# ControlBoard.net
KiCad netlist of a schematic drawn in EAGLE
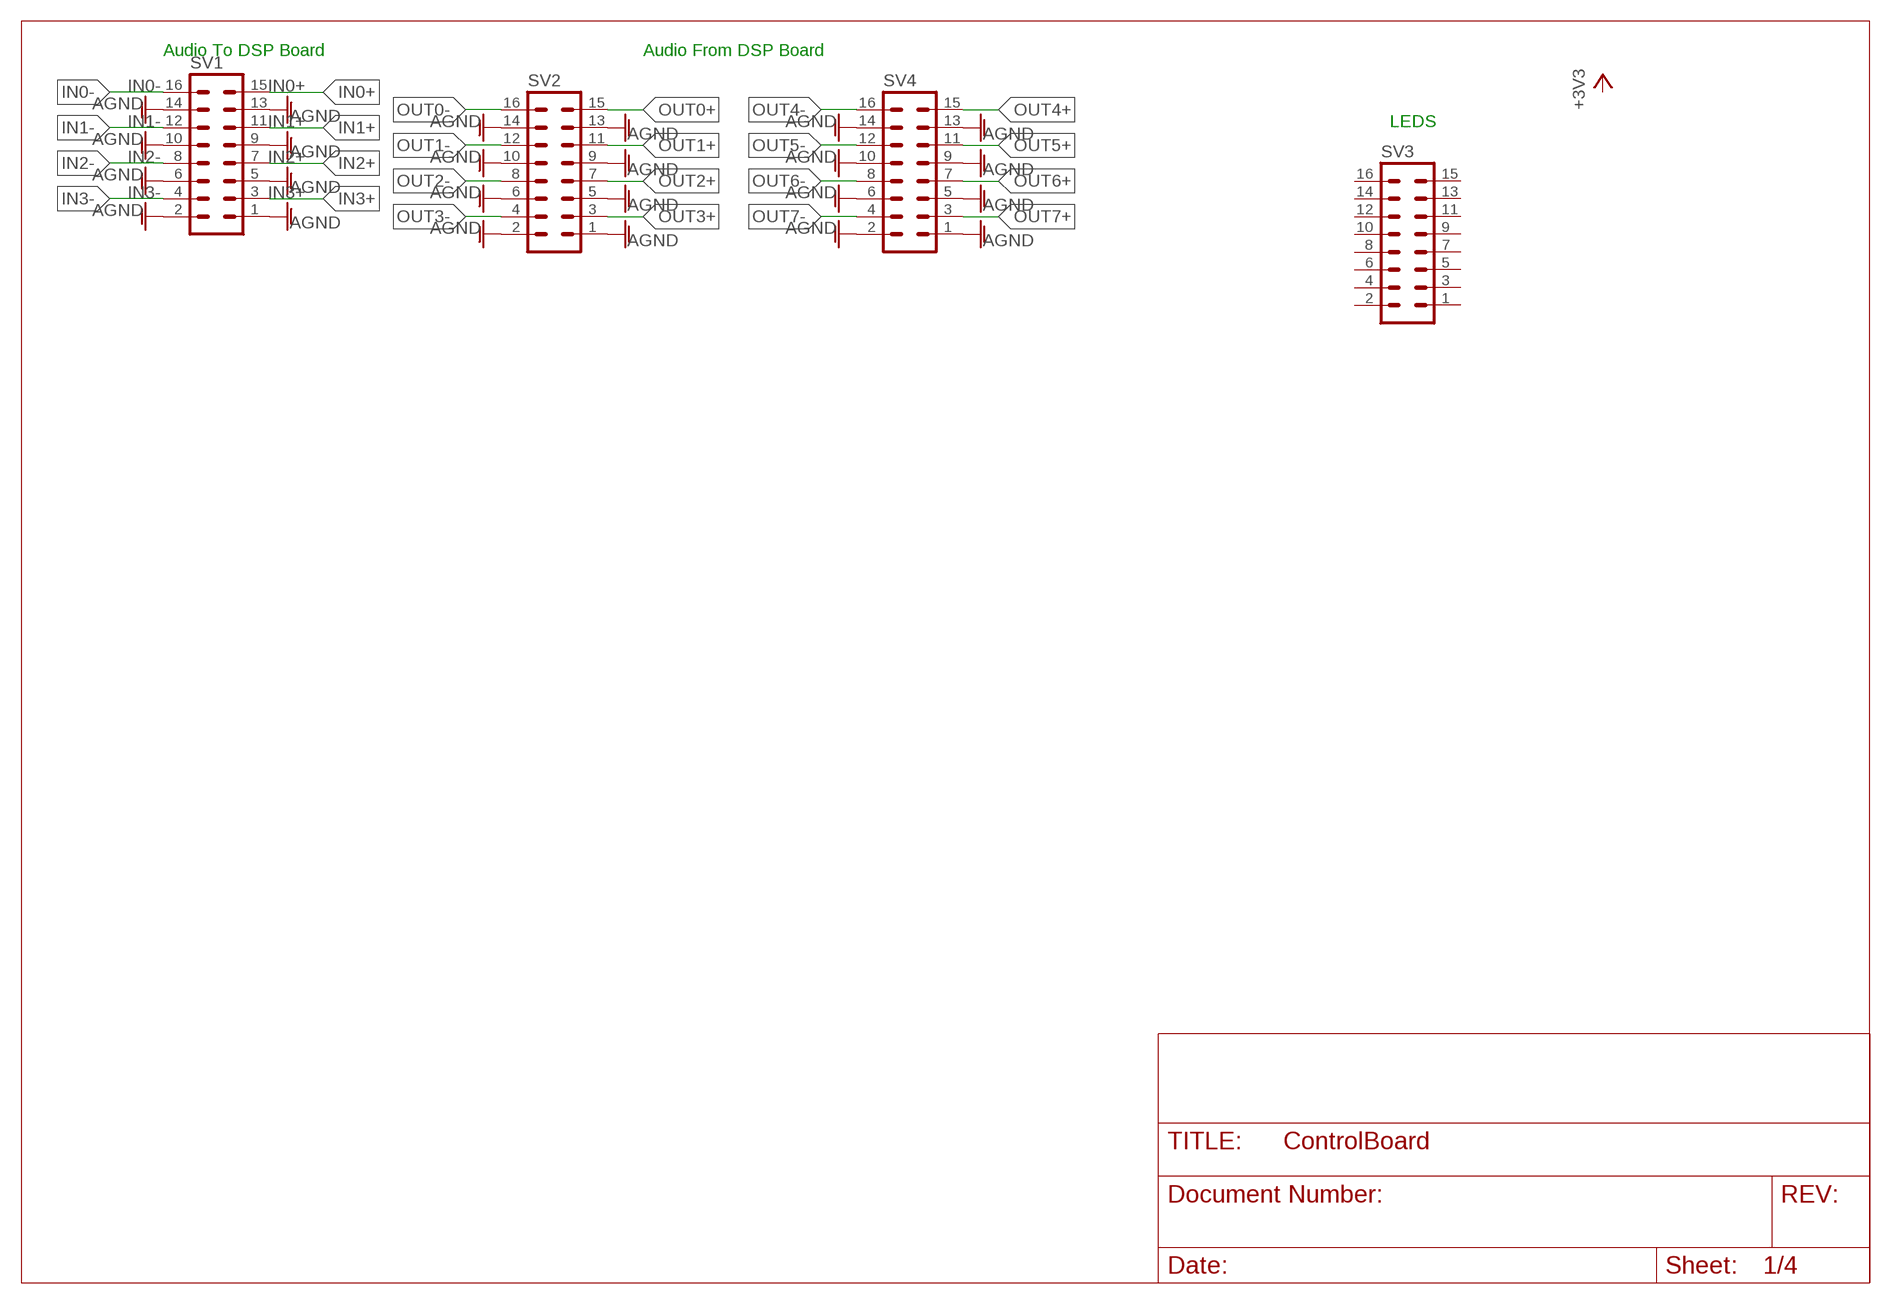
[diagram p0: schematic, sheet 1]
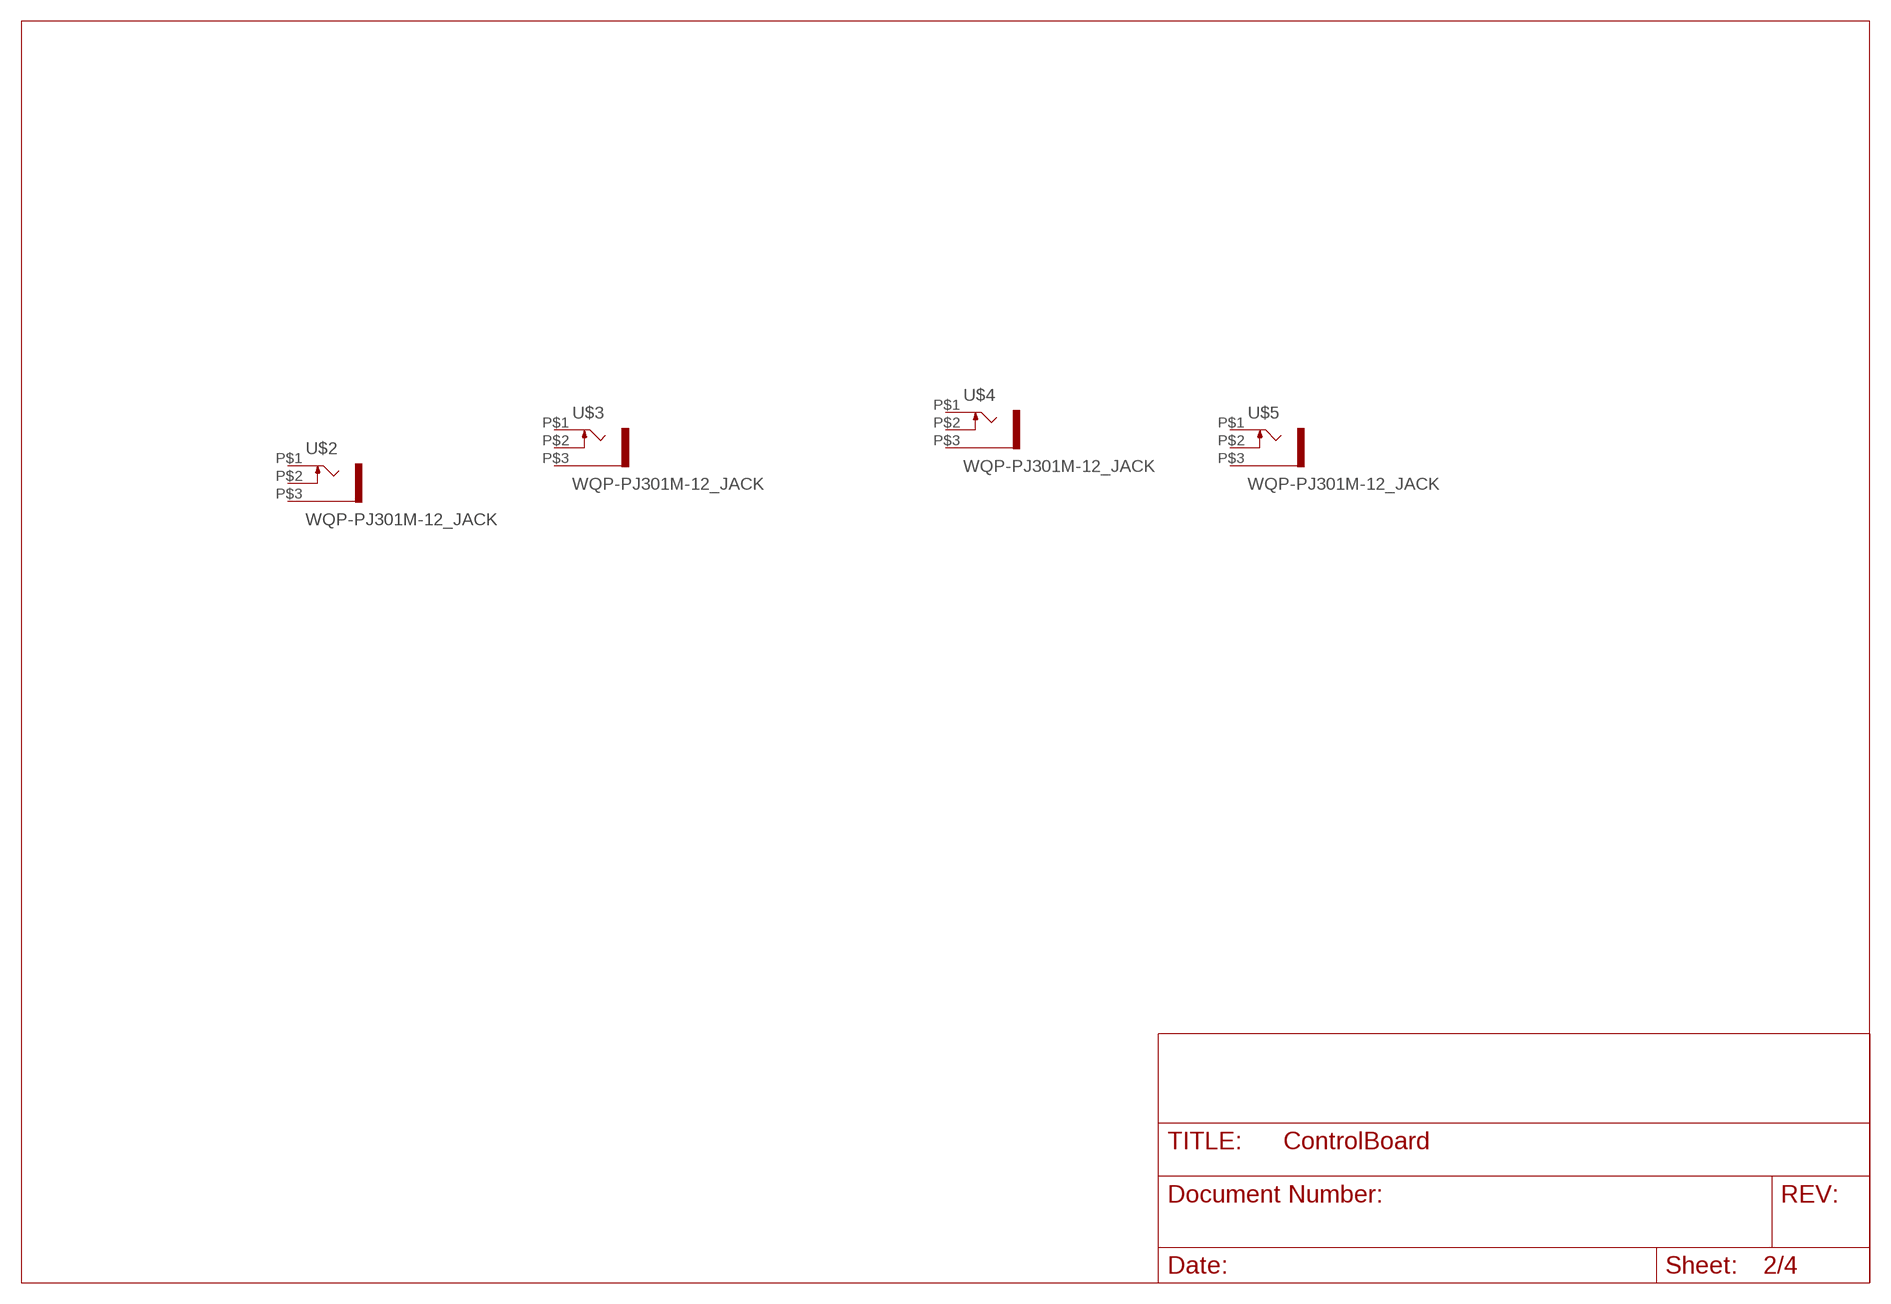
[diagram p1: schematic, sheet 2]
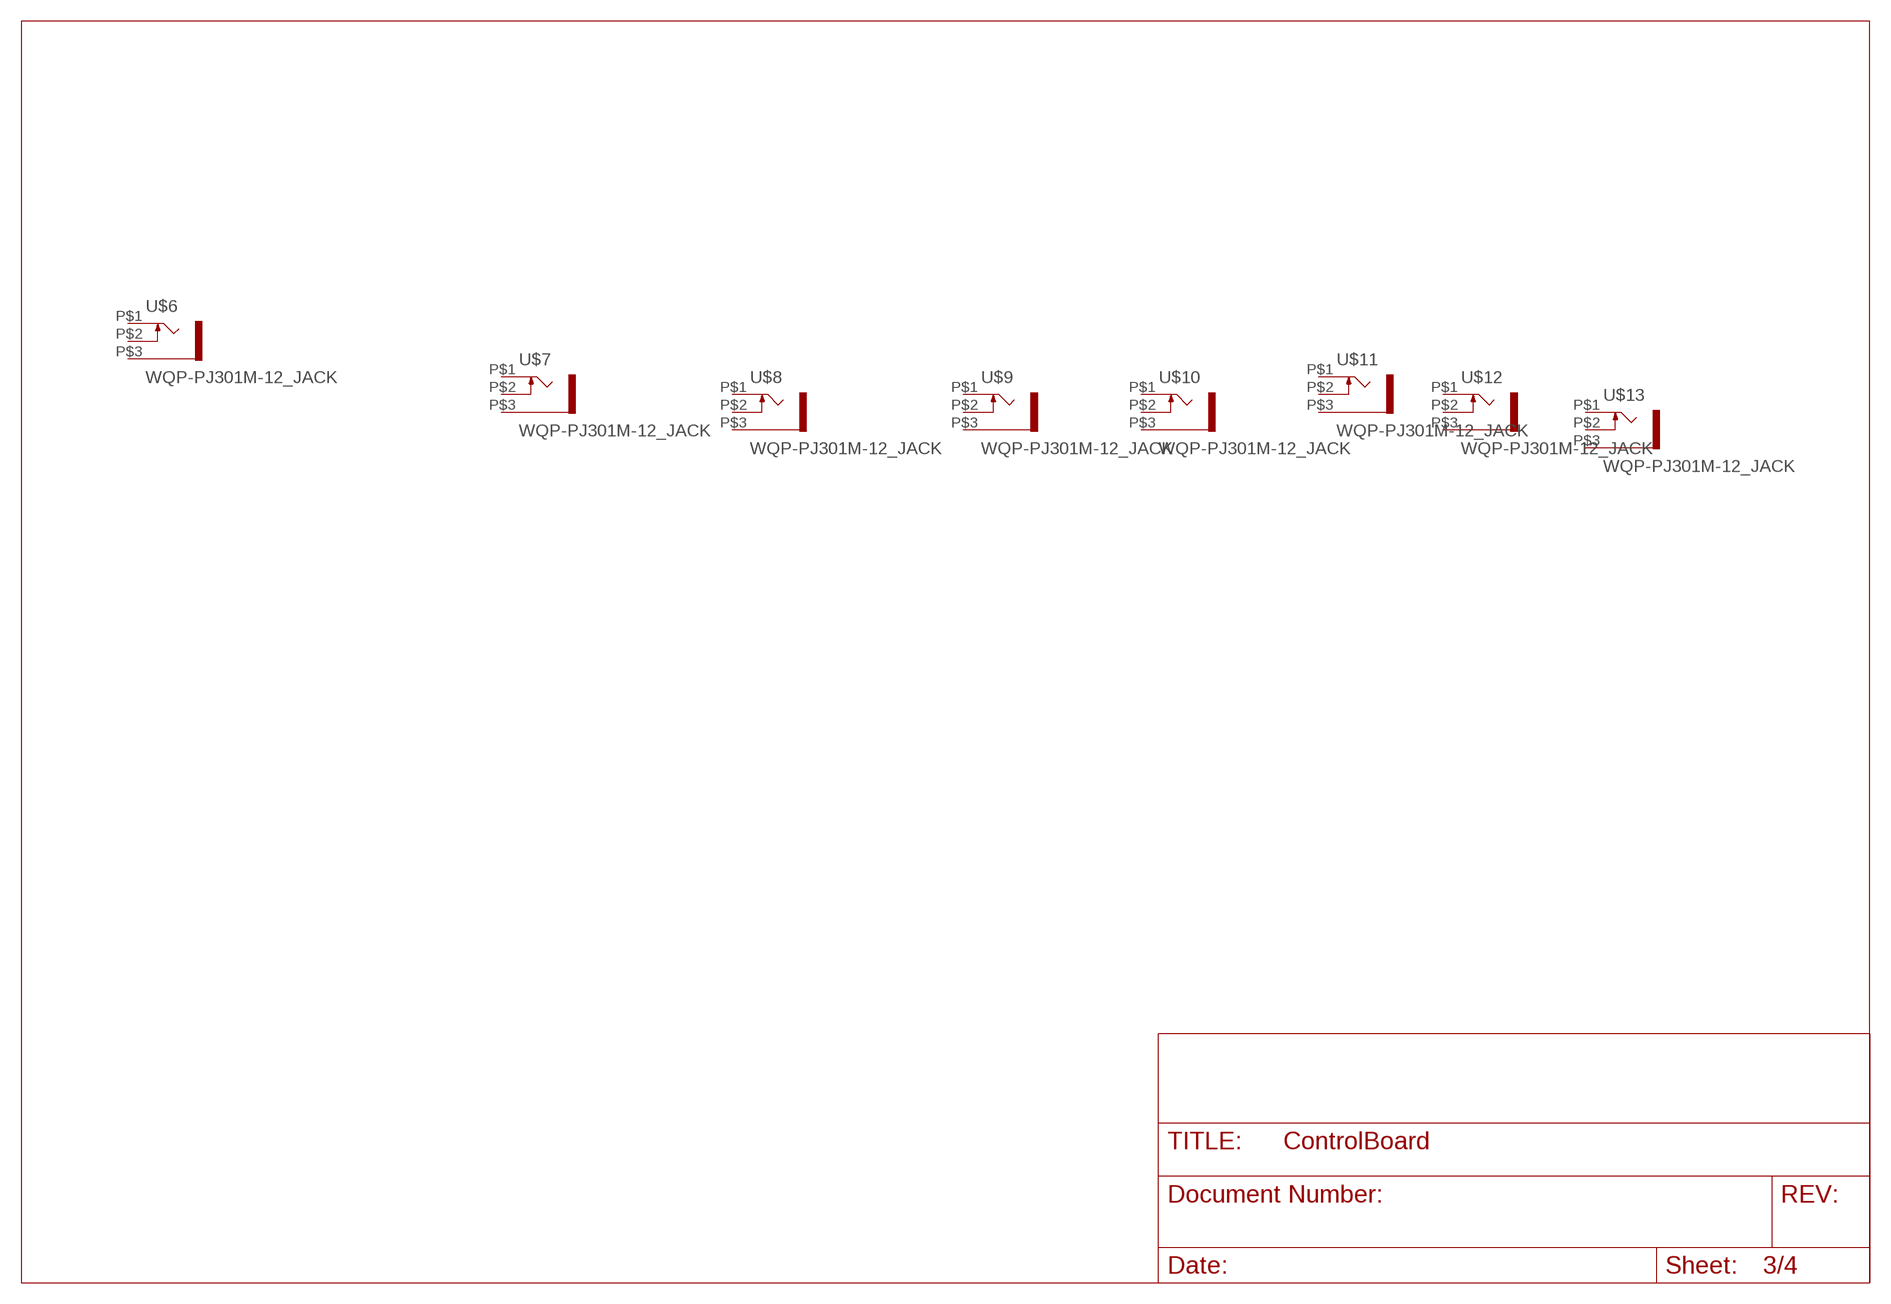
[diagram p2: schematic, sheet 3]
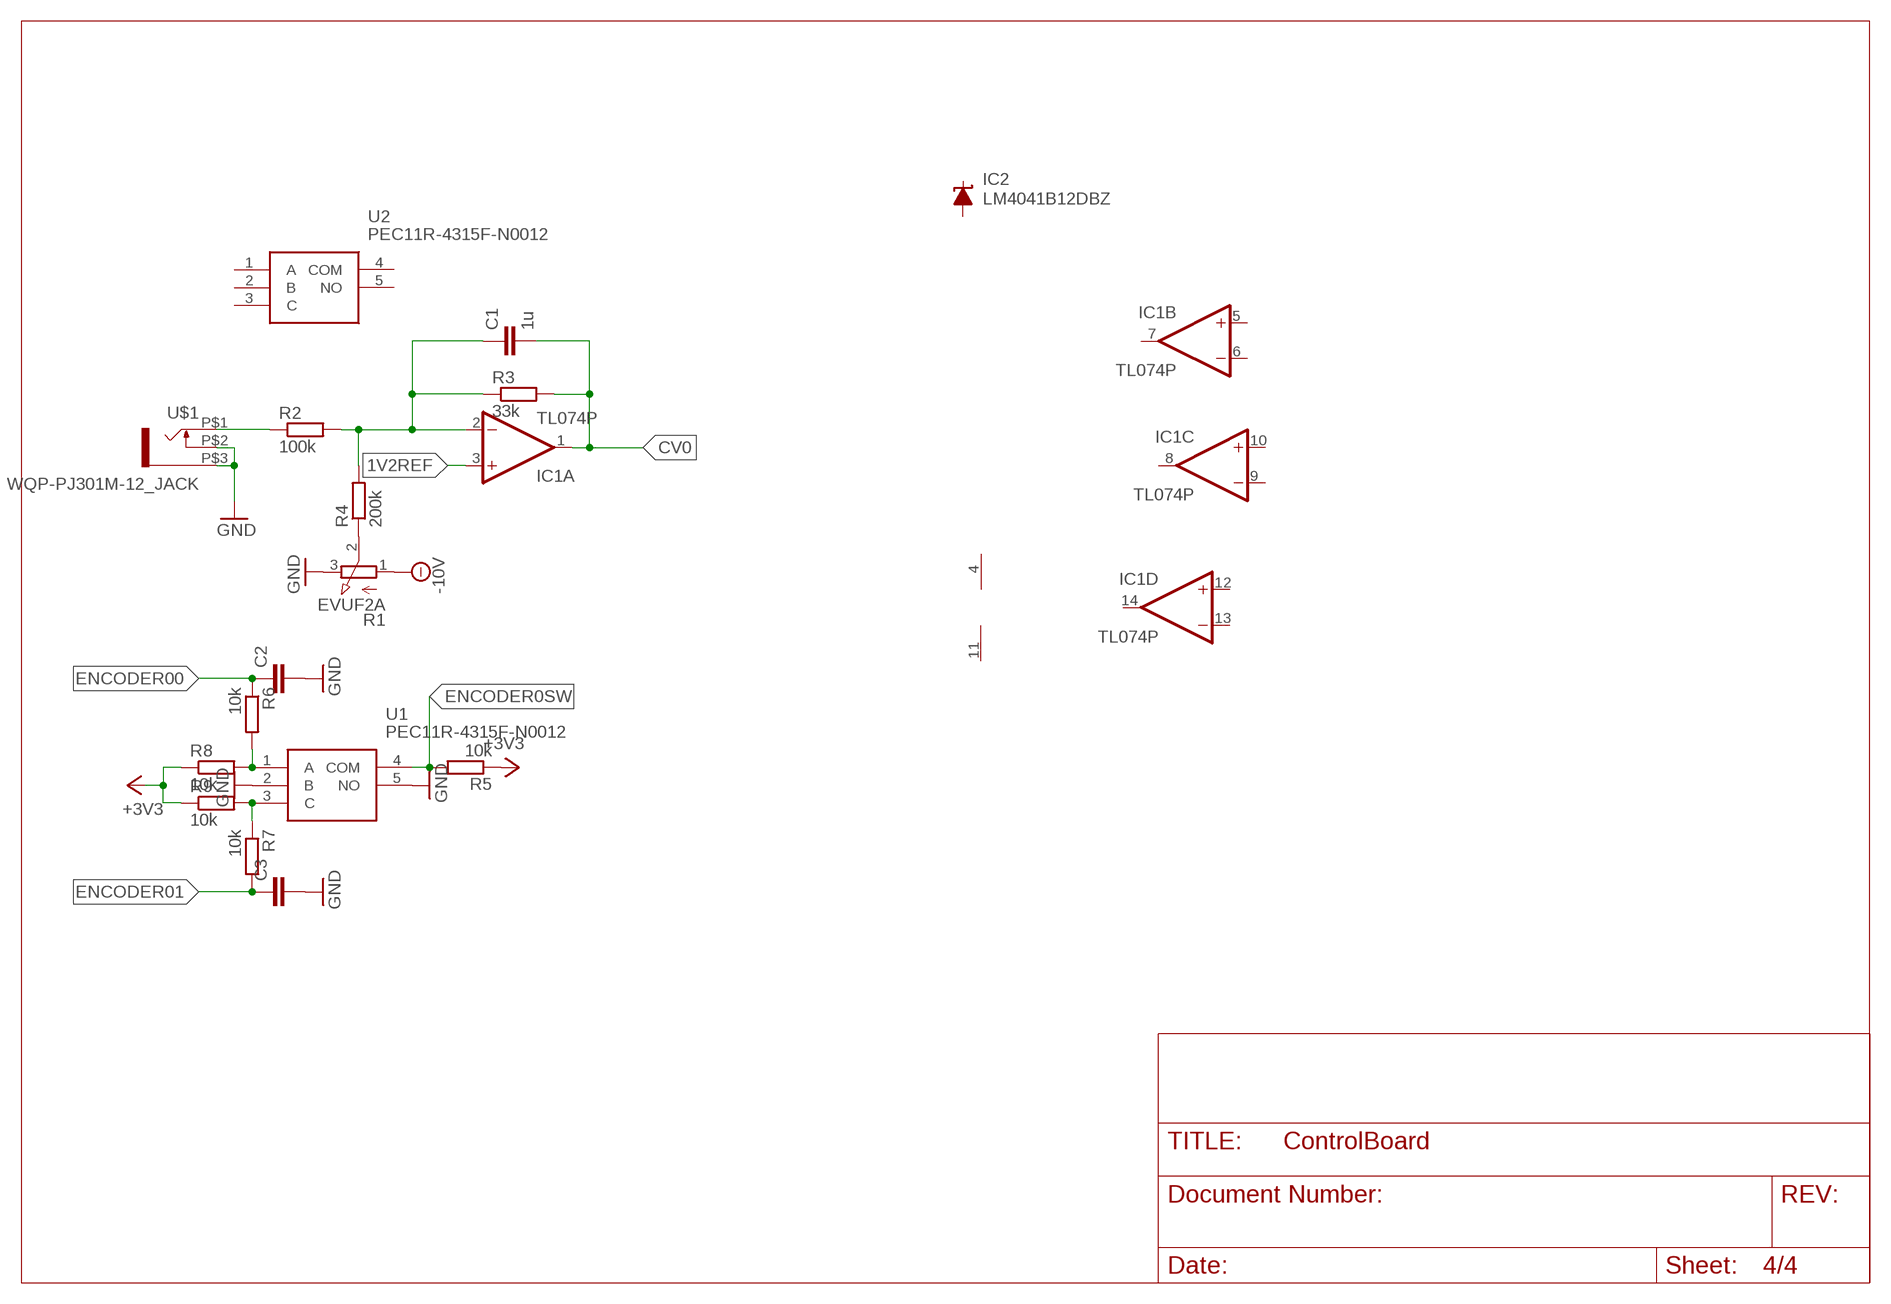
[diagram p3: schematic, sheet 4]

(export (version "E")
  (design (tool "Eeschema 10.0.6"))
  (components
    (comp (ref "U$2")
      (value "WQP-PJ301M-12_JACK")
      (footprint "eagle-import:WQP-PJ301M-12_JACK")
      (libsource (lib "eagle-import") (part "WQP-PJ301M-12_JACK"))
    )
    (comp (ref "U$3")
      (value "WQP-PJ301M-12_JACK")
      (footprint "eagle-import:WQP-PJ301M-12_JACK")
      (libsource (lib "eagle-import") (part "WQP-PJ301M-12_JACK"))
    )
    (comp (ref "U$4")
      (value "WQP-PJ301M-12_JACK")
      (footprint "eagle-import:WQP-PJ301M-12_JACK")
      (libsource (lib "eagle-import") (part "WQP-PJ301M-12_JACK"))
    )
    (comp (ref "U$5")
      (value "WQP-PJ301M-12_JACK")
      (footprint "eagle-import:WQP-PJ301M-12_JACK")
      (libsource (lib "eagle-import") (part "WQP-PJ301M-12_JACK"))
    )
    (comp (ref "C1")
      (value "1u")
      (footprint "eagle-import:C0805")
      (libsource (lib "eagle-import") (part "C-EUC0805"))
    )
    (comp (ref "C2")
      (value "C-EUC0805")
      (footprint "eagle-import:C0805")
      (libsource (lib "eagle-import") (part "C-EUC0805"))
    )
    (comp (ref "C3")
      (value "C-EUC0805")
      (footprint "eagle-import:C0805")
      (libsource (lib "eagle-import") (part "C-EUC0805"))
    )
    (comp (ref "IC1")
      (value "TL074P")
      (footprint "eagle-import:DIL14")
      (libsource (lib "eagle-import") (part "TL074P"))
    )
    (comp (ref "IC2")
      (value "LM4041B12DBZ")
      (footprint "eagle-import:DBZ_R-PDSO-G3")
      (fields (field (name "MPN") "LM4041B12IDBZR"))
      (libsource (lib "eagle-import") (part "LM4041DBZB12"))
    )
    (comp (ref "R1")
      (value "EVUF2A")
      (footprint "eagle-import:EVUF")
      (libsource (lib "eagle-import") (part "EVUAF2"))
    )
    (comp (ref "R2")
      (value "100k")
      (footprint "eagle-import:R0805")
      (libsource (lib "eagle-import") (part "R-EU_R0805"))
    )
    (comp (ref "R3")
      (value "33k")
      (footprint "eagle-import:R0805")
      (libsource (lib "eagle-import") (part "R-EU_R0805"))
    )
    (comp (ref "R4")
      (value "200k")
      (footprint "eagle-import:R0805")
      (libsource (lib "eagle-import") (part "R-EU_R0805"))
    )
    (comp (ref "R5")
      (value "10k")
      (footprint "eagle-import:R0805")
      (libsource (lib "eagle-import") (part "R-EU_R0805"))
    )
    (comp (ref "R6")
      (value "10k")
      (footprint "eagle-import:R0805")
      (libsource (lib "eagle-import") (part "R-EU_R0805"))
    )
    (comp (ref "R7")
      (value "10k")
      (footprint "eagle-import:R0805")
      (libsource (lib "eagle-import") (part "R-EU_R0805"))
    )
    (comp (ref "R8")
      (value "10k")
      (footprint "eagle-import:R0805")
      (libsource (lib "eagle-import") (part "R-EU_R0805"))
    )
    (comp (ref "R9")
      (value "10k")
      (footprint "eagle-import:R0805")
      (libsource (lib "eagle-import") (part "R-EU_R0805"))
    )
    (comp (ref "U$1")
      (value "WQP-PJ301M-12_JACK")
      (footprint "eagle-import:WQP-PJ301M-12_JACK")
      (libsource (lib "eagle-import") (part "WQP-PJ301M-12_JACK"))
    )
    (comp (ref "U1")
      (value "PEC11R-4315F-N0012")
      (footprint "eagle-import:PEC12R-4XXXF-SXXXX_1")
      (fields (field (name "MOUSER_PART_NUMBER") "652-PEC11R4315FN0012"))
      (libsource (lib "eagle-import") (part "PEC11R-4315F-N0012"))
    )
    (comp (ref "U2")
      (value "PEC11R-4315F-N0012")
      (footprint "eagle-import:PEC12R-4XXXF-SXXXX_1")
      (fields (field (name "MOUSER_PART_NUMBER") "652-PEC11R4315FN0012"))
      (libsource (lib "eagle-import") (part "PEC11R-4315F-N0012"))
    )
    (comp (ref "SV1")
      (value "MA08-2")
      (footprint "eagle-import:MA08-2")
      (libsource (lib "eagle-import") (part "MA08-2"))
    )
    (comp (ref "SV2")
      (value "MA08-2")
      (footprint "eagle-import:MA08-2")
      (libsource (lib "eagle-import") (part "MA08-2"))
    )
    (comp (ref "SV3")
      (value "MA08-2")
      (footprint "eagle-import:MA08-2")
      (libsource (lib "eagle-import") (part "MA08-2"))
    )
    (comp (ref "SV4")
      (value "MA08-2")
      (footprint "eagle-import:MA08-2")
      (libsource (lib "eagle-import") (part "MA08-2"))
    )
    (comp (ref "U$6")
      (value "WQP-PJ301M-12_JACK")
      (footprint "eagle-import:WQP-PJ301M-12_JACK")
      (libsource (lib "eagle-import") (part "WQP-PJ301M-12_JACK"))
    )
    (comp (ref "U$7")
      (value "WQP-PJ301M-12_JACK")
      (footprint "eagle-import:WQP-PJ301M-12_JACK")
      (libsource (lib "eagle-import") (part "WQP-PJ301M-12_JACK"))
    )
    (comp (ref "U$8")
      (value "WQP-PJ301M-12_JACK")
      (footprint "eagle-import:WQP-PJ301M-12_JACK")
      (libsource (lib "eagle-import") (part "WQP-PJ301M-12_JACK"))
    )
    (comp (ref "U$9")
      (value "WQP-PJ301M-12_JACK")
      (footprint "eagle-import:WQP-PJ301M-12_JACK")
      (libsource (lib "eagle-import") (part "WQP-PJ301M-12_JACK"))
    )
    (comp (ref "U$10")
      (value "WQP-PJ301M-12_JACK")
      (footprint "eagle-import:WQP-PJ301M-12_JACK")
      (libsource (lib "eagle-import") (part "WQP-PJ301M-12_JACK"))
    )
    (comp (ref "U$11")
      (value "WQP-PJ301M-12_JACK")
      (footprint "eagle-import:WQP-PJ301M-12_JACK")
      (libsource (lib "eagle-import") (part "WQP-PJ301M-12_JACK"))
    )
    (comp (ref "U$12")
      (value "WQP-PJ301M-12_JACK")
      (footprint "eagle-import:WQP-PJ301M-12_JACK")
      (libsource (lib "eagle-import") (part "WQP-PJ301M-12_JACK"))
    )
    (comp (ref "U$13")
      (value "WQP-PJ301M-12_JACK")
      (footprint "eagle-import:WQP-PJ301M-12_JACK")
      (libsource (lib "eagle-import") (part "WQP-PJ301M-12_JACK"))
    )
  )
  (nets
    (net (code "1") (name "+3V3") (class "Default")
      (node (ref "R5") (pin "1") (pinfunction "1_1") (pintype "passive"))
      (node (ref "R8") (pin "1") (pinfunction "1_1") (pintype "passive"))
      (node (ref "R9") (pin "1") (pinfunction "1_1") (pintype "passive"))
    )
    (net (code "2") (name "-10V") (class "Default")
      (node (ref "R1") (pin "1") (pinfunction "A_1") (pintype "passive"))
    )
    (net (code "3") (name "1V2REF") (class "Default")
      (node (ref "IC1") (pin "3") (pinfunction "+IN_3") (pintype "input"))
    )
    (net (code "4") (name "AGND") (class "Default")
      (node (ref "SV1") (pin "1") (pinfunction "1_1") (pintype "passive"))
      (node (ref "SV1") (pin "10") (pinfunction "10_10") (pintype "passive"))
      (node (ref "SV1") (pin "13") (pinfunction "13_13") (pintype "passive"))
      (node (ref "SV1") (pin "14") (pinfunction "14_14") (pintype "passive"))
      (node (ref "SV1") (pin "2") (pinfunction "2_2") (pintype "passive"))
      (node (ref "SV1") (pin "5") (pinfunction "5_5") (pintype "passive"))
      (node (ref "SV1") (pin "6") (pinfunction "6_6") (pintype "passive"))
      (node (ref "SV1") (pin "9") (pinfunction "9_9") (pintype "passive"))
      (node (ref "SV2") (pin "1") (pinfunction "1_1") (pintype "passive"))
      (node (ref "SV2") (pin "10") (pinfunction "10_10") (pintype "passive"))
      (node (ref "SV2") (pin "13") (pinfunction "13_13") (pintype "passive"))
      (node (ref "SV2") (pin "14") (pinfunction "14_14") (pintype "passive"))
      (node (ref "SV2") (pin "2") (pinfunction "2_2") (pintype "passive"))
      (node (ref "SV2") (pin "5") (pinfunction "5_5") (pintype "passive"))
      (node (ref "SV2") (pin "6") (pinfunction "6_6") (pintype "passive"))
      (node (ref "SV2") (pin "9") (pinfunction "9_9") (pintype "passive"))
      (node (ref "SV4") (pin "1") (pinfunction "1_1") (pintype "passive"))
      (node (ref "SV4") (pin "10") (pinfunction "10_10") (pintype "passive"))
      (node (ref "SV4") (pin "13") (pinfunction "13_13") (pintype "passive"))
      (node (ref "SV4") (pin "14") (pinfunction "14_14") (pintype "passive"))
      (node (ref "SV4") (pin "2") (pinfunction "2_2") (pintype "passive"))
      (node (ref "SV4") (pin "5") (pinfunction "5_5") (pintype "passive"))
      (node (ref "SV4") (pin "6") (pinfunction "6_6") (pintype "passive"))
      (node (ref "SV4") (pin "9") (pinfunction "9_9") (pintype "passive"))
    )
    (net (code "5") (name "CV0") (class "Default")
      (node (ref "C1") (pin "2") (pinfunction "2_2") (pintype "passive"))
      (node (ref "IC1") (pin "1") (pinfunction "OUT_1") (pintype "output"))
      (node (ref "R3") (pin "2") (pinfunction "2_2") (pintype "passive"))
    )
    (net (code "6") (name "ENCODER00") (class "Default")
      (node (ref "C2") (pin "1") (pinfunction "1_1") (pintype "passive"))
      (node (ref "R6") (pin "1") (pinfunction "1_1") (pintype "passive"))
    )
    (net (code "7") (name "ENCODER0SW") (class "Default")
      (node (ref "R5") (pin "2") (pinfunction "2_2") (pintype "passive"))
      (node (ref "U1") (pin "4") (pinfunction "COM_4") (pintype "bidirectional"))
    )
    (net (code "8") (name "ENCODER01") (class "Default")
      (node (ref "C3") (pin "1") (pinfunction "1_1") (pintype "passive"))
      (node (ref "R7") (pin "2") (pinfunction "2_2") (pintype "passive"))
    )
    (net (code "9") (name "GND") (class "Default")
      (node (ref "C2") (pin "2") (pinfunction "2_2") (pintype "passive"))
      (node (ref "C3") (pin "2") (pinfunction "2_2") (pintype "passive"))
      (node (ref "R1") (pin "3") (pinfunction "E_3") (pintype "passive"))
      (node (ref "U$1") (pin "P$2") (pinfunction "3_P$2") (pintype "passive"))
      (node (ref "U$1") (pin "P$3") (pinfunction "1_P$3") (pintype "passive"))
      (node (ref "U1") (pin "2") (pinfunction "B_2") (pintype "bidirectional"))
      (node (ref "U1") (pin "5") (pinfunction "NO_5") (pintype "bidirectional"))
    )
    (net (code "10") (name "IN0+") (class "Default")
      (node (ref "SV1") (pin "15") (pinfunction "15_15") (pintype "passive"))
    )
    (net (code "11") (name "IN0-") (class "Default")
      (node (ref "SV1") (pin "16") (pinfunction "16_16") (pintype "passive"))
    )
    (net (code "12") (name "IN1+") (class "Default")
      (node (ref "SV1") (pin "11") (pinfunction "11_11") (pintype "passive"))
    )
    (net (code "13") (name "IN1-") (class "Default")
      (node (ref "SV1") (pin "12") (pinfunction "12_12") (pintype "passive"))
    )
    (net (code "14") (name "IN2+") (class "Default")
      (node (ref "SV1") (pin "7") (pinfunction "7_7") (pintype "passive"))
    )
    (net (code "15") (name "IN2-") (class "Default")
      (node (ref "SV1") (pin "8") (pinfunction "8_8") (pintype "passive"))
    )
    (net (code "16") (name "IN3+") (class "Default")
      (node (ref "SV1") (pin "3") (pinfunction "3_3") (pintype "passive"))
    )
    (net (code "17") (name "IN3-") (class "Default")
      (node (ref "SV1") (pin "4") (pinfunction "4_4") (pintype "passive"))
    )
    (net (code "18") (name "Net-(IC1A--IN)") (class "Default")
      (node (ref "C1") (pin "1") (pinfunction "1_1") (pintype "passive"))
      (node (ref "IC1") (pin "2") (pinfunction "-IN_2") (pintype "input"))
      (node (ref "R2") (pin "2") (pinfunction "2_2") (pintype "passive"))
      (node (ref "R3") (pin "1") (pinfunction "1_1") (pintype "passive"))
      (node (ref "R4") (pin "2") (pinfunction "2_2") (pintype "passive"))
    )
    (net (code "19") (name "Net-(R1-S)") (class "Default")
      (node (ref "R1") (pin "2") (pinfunction "S_2") (pintype "passive"))
      (node (ref "R4") (pin "1") (pinfunction "1_1") (pintype "passive"))
    )
    (net (code "20") (name "Net-(U$1-2)") (class "Default")
      (node (ref "R2") (pin "1") (pinfunction "1_1") (pintype "passive"))
      (node (ref "U$1") (pin "P$1") (pinfunction "2_P$1") (pintype "passive"))
    )
    (net (code "21") (name "Net-(U1-A)") (class "Default")
      (node (ref "R6") (pin "2") (pinfunction "2_2") (pintype "passive"))
      (node (ref "R8") (pin "2") (pinfunction "2_2") (pintype "passive"))
      (node (ref "U1") (pin "1") (pinfunction "A_1") (pintype "bidirectional"))
    )
    (net (code "22") (name "Net-(U1-C)") (class "Default")
      (node (ref "R7") (pin "1") (pinfunction "1_1") (pintype "passive"))
      (node (ref "R9") (pin "2") (pinfunction "2_2") (pintype "passive"))
      (node (ref "U1") (pin "3") (pinfunction "C_3") (pintype "bidirectional"))
    )
    (net (code "23") (name "OUT0+") (class "Default")
      (node (ref "SV2") (pin "15") (pinfunction "15_15") (pintype "passive"))
    )
    (net (code "24") (name "OUT0-") (class "Default")
      (node (ref "SV2") (pin "16") (pinfunction "16_16") (pintype "passive"))
    )
    (net (code "25") (name "OUT1+") (class "Default")
      (node (ref "SV2") (pin "11") (pinfunction "11_11") (pintype "passive"))
    )
    (net (code "26") (name "OUT1-") (class "Default")
      (node (ref "SV2") (pin "12") (pinfunction "12_12") (pintype "passive"))
    )
    (net (code "27") (name "OUT2+") (class "Default")
      (node (ref "SV2") (pin "7") (pinfunction "7_7") (pintype "passive"))
    )
    (net (code "28") (name "OUT2-") (class "Default")
      (node (ref "SV2") (pin "8") (pinfunction "8_8") (pintype "passive"))
    )
    (net (code "29") (name "OUT3+") (class "Default")
      (node (ref "SV2") (pin "3") (pinfunction "3_3") (pintype "passive"))
    )
    (net (code "30") (name "OUT3-") (class "Default")
      (node (ref "SV2") (pin "4") (pinfunction "4_4") (pintype "passive"))
    )
    (net (code "31") (name "OUT4+") (class "Default")
      (node (ref "SV4") (pin "15") (pinfunction "15_15") (pintype "passive"))
    )
    (net (code "32") (name "OUT4-") (class "Default")
      (node (ref "SV4") (pin "16") (pinfunction "16_16") (pintype "passive"))
    )
    (net (code "33") (name "OUT5+") (class "Default")
      (node (ref "SV4") (pin "11") (pinfunction "11_11") (pintype "passive"))
    )
    (net (code "34") (name "OUT5-") (class "Default")
      (node (ref "SV4") (pin "12") (pinfunction "12_12") (pintype "passive"))
    )
    (net (code "35") (name "OUT6+") (class "Default")
      (node (ref "SV4") (pin "7") (pinfunction "7_7") (pintype "passive"))
    )
    (net (code "36") (name "OUT6-") (class "Default")
      (node (ref "SV4") (pin "8") (pinfunction "8_8") (pintype "passive"))
    )
    (net (code "37") (name "OUT7+") (class "Default")
      (node (ref "SV4") (pin "3") (pinfunction "3_3") (pintype "passive"))
    )
    (net (code "38") (name "OUT7-") (class "Default")
      (node (ref "SV4") (pin "4") (pinfunction "4_4") (pintype "passive"))
    )
    (net (code "39") (name "V+") (class "Default")
      (node (ref "IC1") (pin "4") (pinfunction "V+_4") (pintype "power_in"))
    )
    (net (code "40") (name "V-") (class "Default")
      (node (ref "IC1") (pin "11") (pinfunction "V-_11") (pintype "power_in"))
    )
    (net (code "41") (name "unconnected-(IC1B-+IN-Pad5)") (class "Default")
      (node (ref "IC1") (pin "5") (pinfunction "+IN_5") (pintype "input"))
    )
    (net (code "42") (name "unconnected-(IC1B--IN-Pad6)") (class "Default")
      (node (ref "IC1") (pin "6") (pinfunction "-IN_6") (pintype "input"))
    )
    (net (code "43") (name "unconnected-(IC1B-OUT-Pad7)") (class "Default")
      (node (ref "IC1") (pin "7") (pinfunction "OUT_7") (pintype "output"))
    )
    (net (code "44") (name "unconnected-(IC1C-+IN-Pad10)") (class "Default")
      (node (ref "IC1") (pin "10") (pinfunction "+IN_10") (pintype "input"))
    )
    (net (code "45") (name "unconnected-(IC1C--IN-Pad9)") (class "Default")
      (node (ref "IC1") (pin "9") (pinfunction "-IN_9") (pintype "input"))
    )
    (net (code "46") (name "unconnected-(IC1C-OUT-Pad8)") (class "Default")
      (node (ref "IC1") (pin "8") (pinfunction "OUT_8") (pintype "output"))
    )
    (net (code "47") (name "unconnected-(IC1D-+IN-Pad12)") (class "Default")
      (node (ref "IC1") (pin "12") (pinfunction "+IN_12") (pintype "input"))
    )
    (net (code "48") (name "unconnected-(IC1D--IN-Pad13)") (class "Default")
      (node (ref "IC1") (pin "13") (pinfunction "-IN_13") (pintype "input"))
    )
    (net (code "49") (name "unconnected-(IC1D-OUT-Pad14)") (class "Default")
      (node (ref "IC1") (pin "14") (pinfunction "OUT_14") (pintype "output"))
    )
    (net (code "50") (name "unconnected-(IC2-A-Pad2)") (class "Default")
      (node (ref "IC2") (pin "2") (pinfunction "A_2") (pintype "passive"))
    )
    (net (code "51") (name "unconnected-(IC2-C-Pad1)") (class "Default")
      (node (ref "IC2") (pin "1") (pinfunction "C_1") (pintype "passive"))
    )
    (net (code "52") (name "unconnected-(SV3-Pad1)") (class "Default")
      (node (ref "SV3") (pin "1") (pinfunction "1_1") (pintype "passive"))
    )
    (net (code "53") (name "unconnected-(SV3-Pad2)") (class "Default")
      (node (ref "SV3") (pin "2") (pinfunction "2_2") (pintype "passive"))
    )
    (net (code "54") (name "unconnected-(SV3-Pad3)") (class "Default")
      (node (ref "SV3") (pin "3") (pinfunction "3_3") (pintype "passive"))
    )
    (net (code "55") (name "unconnected-(SV3-Pad4)") (class "Default")
      (node (ref "SV3") (pin "4") (pinfunction "4_4") (pintype "passive"))
    )
    (net (code "56") (name "unconnected-(SV3-Pad5)") (class "Default")
      (node (ref "SV3") (pin "5") (pinfunction "5_5") (pintype "passive"))
    )
    (net (code "57") (name "unconnected-(SV3-Pad6)") (class "Default")
      (node (ref "SV3") (pin "6") (pinfunction "6_6") (pintype "passive"))
    )
    (net (code "58") (name "unconnected-(SV3-Pad7)") (class "Default")
      (node (ref "SV3") (pin "7") (pinfunction "7_7") (pintype "passive"))
    )
    (net (code "59") (name "unconnected-(SV3-Pad8)") (class "Default")
      (node (ref "SV3") (pin "8") (pinfunction "8_8") (pintype "passive"))
    )
    (net (code "60") (name "unconnected-(SV3-Pad9)") (class "Default")
      (node (ref "SV3") (pin "9") (pinfunction "9_9") (pintype "passive"))
    )
    (net (code "61") (name "unconnected-(SV3-Pad10)") (class "Default")
      (node (ref "SV3") (pin "10") (pinfunction "10_10") (pintype "passive"))
    )
    (net (code "62") (name "unconnected-(SV3-Pad11)") (class "Default")
      (node (ref "SV3") (pin "11") (pinfunction "11_11") (pintype "passive"))
    )
    (net (code "63") (name "unconnected-(SV3-Pad12)") (class "Default")
      (node (ref "SV3") (pin "12") (pinfunction "12_12") (pintype "passive"))
    )
    (net (code "64") (name "unconnected-(SV3-Pad13)") (class "Default")
      (node (ref "SV3") (pin "13") (pinfunction "13_13") (pintype "passive"))
    )
    (net (code "65") (name "unconnected-(SV3-Pad14)") (class "Default")
      (node (ref "SV3") (pin "14") (pinfunction "14_14") (pintype "passive"))
    )
    (net (code "66") (name "unconnected-(SV3-Pad15)") (class "Default")
      (node (ref "SV3") (pin "15") (pinfunction "15_15") (pintype "passive"))
    )
    (net (code "67") (name "unconnected-(SV3-Pad16)") (class "Default")
      (node (ref "SV3") (pin "16") (pinfunction "16_16") (pintype "passive"))
    )
    (net (code "68") (name "unconnected-(U$2-1-PadP$3)") (class "Default")
      (node (ref "U$2") (pin "P$3") (pinfunction "1_P$3") (pintype "passive"))
    )
    (net (code "69") (name "unconnected-(U$2-2-PadP$1)") (class "Default")
      (node (ref "U$2") (pin "P$1") (pinfunction "2_P$1") (pintype "passive"))
    )
    (net (code "70") (name "unconnected-(U$2-3-PadP$2)") (class "Default")
      (node (ref "U$2") (pin "P$2") (pinfunction "3_P$2") (pintype "passive"))
    )
    (net (code "71") (name "unconnected-(U$3-1-PadP$3)") (class "Default")
      (node (ref "U$3") (pin "P$3") (pinfunction "1_P$3") (pintype "passive"))
    )
    (net (code "72") (name "unconnected-(U$3-2-PadP$1)") (class "Default")
      (node (ref "U$3") (pin "P$1") (pinfunction "2_P$1") (pintype "passive"))
    )
    (net (code "73") (name "unconnected-(U$3-3-PadP$2)") (class "Default")
      (node (ref "U$3") (pin "P$2") (pinfunction "3_P$2") (pintype "passive"))
    )
    (net (code "74") (name "unconnected-(U$4-1-PadP$3)") (class "Default")
      (node (ref "U$4") (pin "P$3") (pinfunction "1_P$3") (pintype "passive"))
    )
    (net (code "75") (name "unconnected-(U$4-2-PadP$1)") (class "Default")
      (node (ref "U$4") (pin "P$1") (pinfunction "2_P$1") (pintype "passive"))
    )
    (net (code "76") (name "unconnected-(U$4-3-PadP$2)") (class "Default")
      (node (ref "U$4") (pin "P$2") (pinfunction "3_P$2") (pintype "passive"))
    )
    (net (code "77") (name "unconnected-(U$5-1-PadP$3)") (class "Default")
      (node (ref "U$5") (pin "P$3") (pinfunction "1_P$3") (pintype "passive"))
    )
    (net (code "78") (name "unconnected-(U$5-2-PadP$1)") (class "Default")
      (node (ref "U$5") (pin "P$1") (pinfunction "2_P$1") (pintype "passive"))
    )
    (net (code "79") (name "unconnected-(U$5-3-PadP$2)") (class "Default")
      (node (ref "U$5") (pin "P$2") (pinfunction "3_P$2") (pintype "passive"))
    )
    (net (code "80") (name "unconnected-(U$6-1-PadP$3)") (class "Default")
      (node (ref "U$6") (pin "P$3") (pinfunction "1_P$3") (pintype "passive"))
    )
    (net (code "81") (name "unconnected-(U$6-2-PadP$1)") (class "Default")
      (node (ref "U$6") (pin "P$1") (pinfunction "2_P$1") (pintype "passive"))
    )
    (net (code "82") (name "unconnected-(U$6-3-PadP$2)") (class "Default")
      (node (ref "U$6") (pin "P$2") (pinfunction "3_P$2") (pintype "passive"))
    )
    (net (code "83") (name "unconnected-(U$7-1-PadP$3)") (class "Default")
      (node (ref "U$7") (pin "P$3") (pinfunction "1_P$3") (pintype "passive"))
    )
    (net (code "84") (name "unconnected-(U$7-2-PadP$1)") (class "Default")
      (node (ref "U$7") (pin "P$1") (pinfunction "2_P$1") (pintype "passive"))
    )
    (net (code "85") (name "unconnected-(U$7-3-PadP$2)") (class "Default")
      (node (ref "U$7") (pin "P$2") (pinfunction "3_P$2") (pintype "passive"))
    )
    (net (code "86") (name "unconnected-(U$8-1-PadP$3)") (class "Default")
      (node (ref "U$8") (pin "P$3") (pinfunction "1_P$3") (pintype "passive"))
    )
    (net (code "87") (name "unconnected-(U$8-2-PadP$1)") (class "Default")
      (node (ref "U$8") (pin "P$1") (pinfunction "2_P$1") (pintype "passive"))
    )
    (net (code "88") (name "unconnected-(U$8-3-PadP$2)") (class "Default")
      (node (ref "U$8") (pin "P$2") (pinfunction "3_P$2") (pintype "passive"))
    )
    (net (code "89") (name "unconnected-(U$9-1-PadP$3)") (class "Default")
      (node (ref "U$9") (pin "P$3") (pinfunction "1_P$3") (pintype "passive"))
    )
    (net (code "90") (name "unconnected-(U$9-2-PadP$1)") (class "Default")
      (node (ref "U$9") (pin "P$1") (pinfunction "2_P$1") (pintype "passive"))
    )
    (net (code "91") (name "unconnected-(U$9-3-PadP$2)") (class "Default")
      (node (ref "U$9") (pin "P$2") (pinfunction "3_P$2") (pintype "passive"))
    )
    (net (code "92") (name "unconnected-(U$10-1-PadP$3)") (class "Default")
      (node (ref "U$10") (pin "P$3") (pinfunction "1_P$3") (pintype "passive"))
    )
    (net (code "93") (name "unconnected-(U$10-2-PadP$1)") (class "Default")
      (node (ref "U$10") (pin "P$1") (pinfunction "2_P$1") (pintype "passive"))
    )
    (net (code "94") (name "unconnected-(U$10-3-PadP$2)") (class "Default")
      (node (ref "U$10") (pin "P$2") (pinfunction "3_P$2") (pintype "passive"))
    )
    (net (code "95") (name "unconnected-(U$11-1-PadP$3)") (class "Default")
      (node (ref "U$11") (pin "P$3") (pinfunction "1_P$3") (pintype "passive"))
    )
    (net (code "96") (name "unconnected-(U$11-2-PadP$1)") (class "Default")
      (node (ref "U$11") (pin "P$1") (pinfunction "2_P$1") (pintype "passive"))
    )
    (net (code "97") (name "unconnected-(U$11-3-PadP$2)") (class "Default")
      (node (ref "U$11") (pin "P$2") (pinfunction "3_P$2") (pintype "passive"))
    )
    (net (code "98") (name "unconnected-(U$12-1-PadP$3)") (class "Default")
      (node (ref "U$12") (pin "P$3") (pinfunction "1_P$3") (pintype "passive"))
    )
    (net (code "99") (name "unconnected-(U$12-2-PadP$1)") (class "Default")
      (node (ref "U$12") (pin "P$1") (pinfunction "2_P$1") (pintype "passive"))
    )
    (net (code "100") (name "unconnected-(U$12-3-PadP$2)") (class "Default")
      (node (ref "U$12") (pin "P$2") (pinfunction "3_P$2") (pintype "passive"))
    )
    (net (code "101") (name "unconnected-(U$13-1-PadP$3)") (class "Default")
      (node (ref "U$13") (pin "P$3") (pinfunction "1_P$3") (pintype "passive"))
    )
    (net (code "102") (name "unconnected-(U$13-2-PadP$1)") (class "Default")
      (node (ref "U$13") (pin "P$1") (pinfunction "2_P$1") (pintype "passive"))
    )
    (net (code "103") (name "unconnected-(U$13-3-PadP$2)") (class "Default")
      (node (ref "U$13") (pin "P$2") (pinfunction "3_P$2") (pintype "passive"))
    )
    (net (code "104") (name "unconnected-(U2-A-Pad1)") (class "Default")
      (node (ref "U2") (pin "1") (pinfunction "A_1") (pintype "bidirectional"))
    )
    (net (code "105") (name "unconnected-(U2-B-Pad2)") (class "Default")
      (node (ref "U2") (pin "2") (pinfunction "B_2") (pintype "bidirectional"))
    )
    (net (code "106") (name "unconnected-(U2-C-Pad3)") (class "Default")
      (node (ref "U2") (pin "3") (pinfunction "C_3") (pintype "bidirectional"))
    )
    (net (code "107") (name "unconnected-(U2-COM-Pad4)") (class "Default")
      (node (ref "U2") (pin "4") (pinfunction "COM_4") (pintype "bidirectional"))
    )
    (net (code "108") (name "unconnected-(U2-NO-Pad5)") (class "Default")
      (node (ref "U2") (pin "5") (pinfunction "NO_5") (pintype "bidirectional"))
    )
  )
)
